# main.net
KiCad netlist of a schematic drawn in Altium Designer
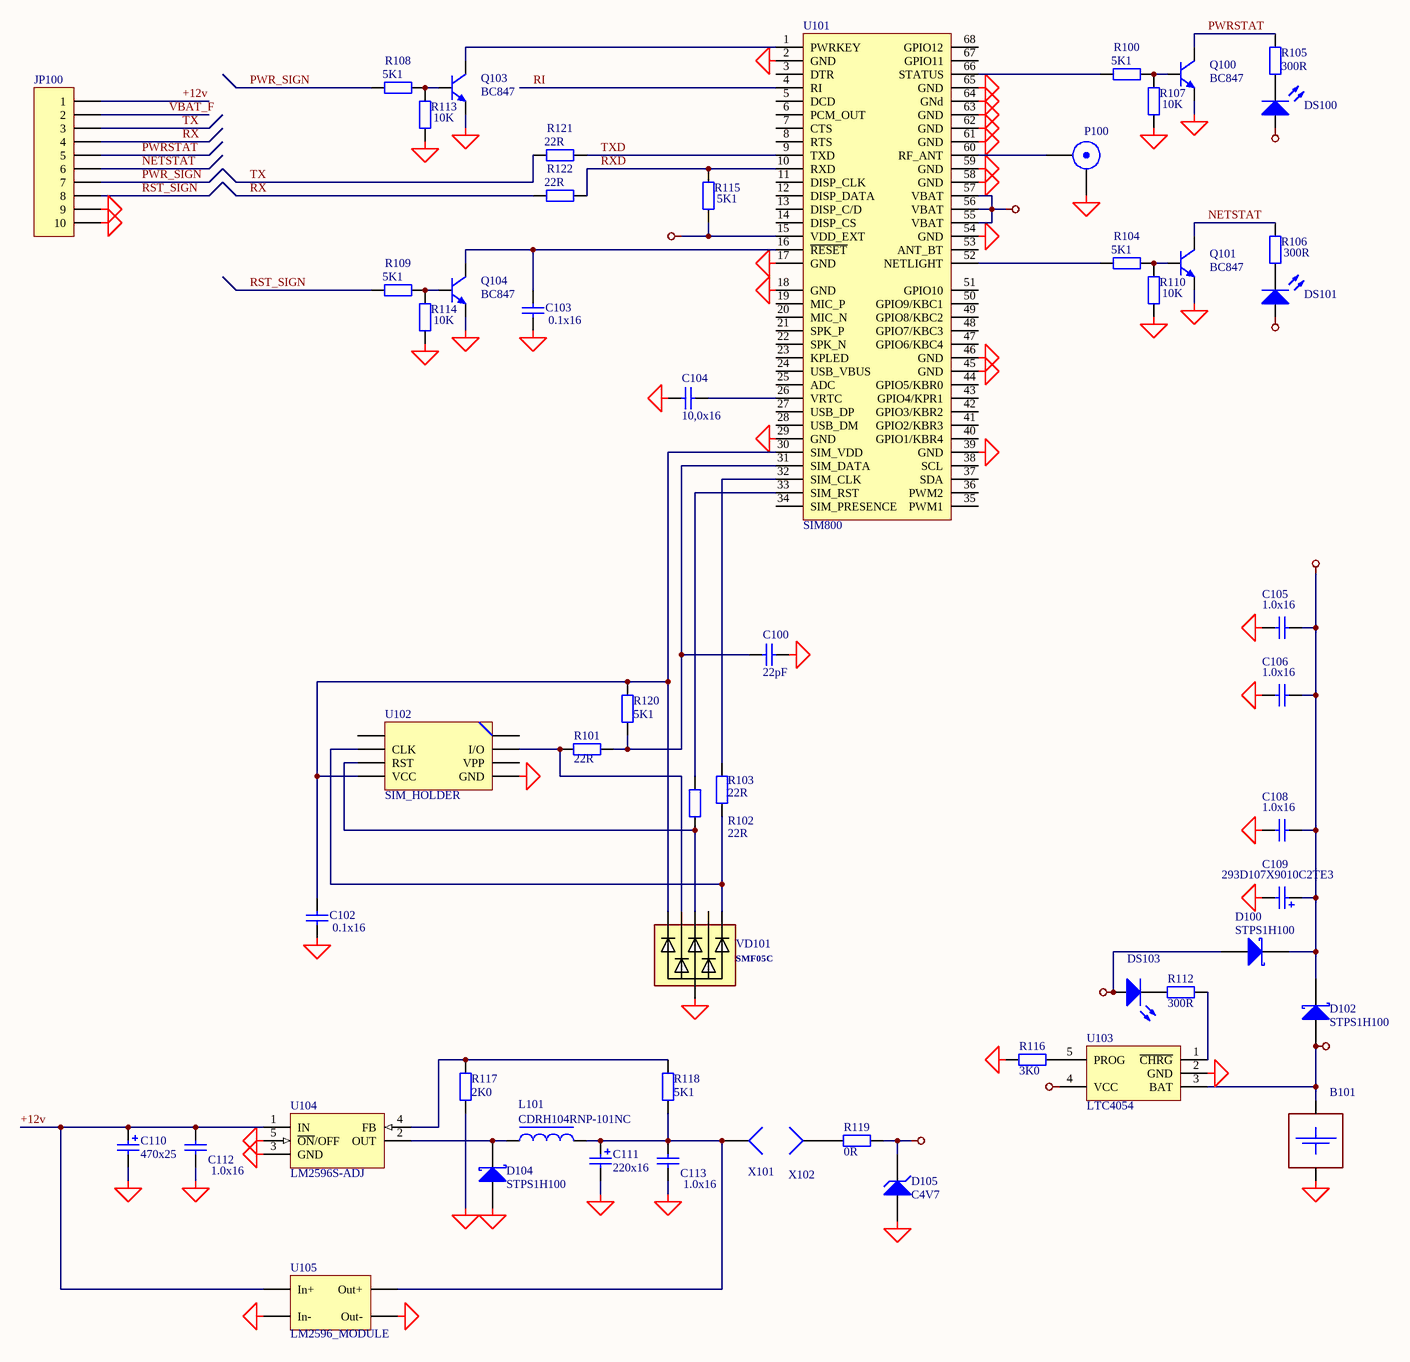
[diagram p0: main.SchDoc]

(export (version "E")
  (design (tool "Eeschema 10.0.6"))
  (components
    (comp (ref "B101")
      (value "BAT18650_HOLDER")
      (footprint "BAT18650_HOLDER")
      (libsource (lib "PAL") (part "BAT18650_HOLDER"))
    )
    (comp (ref "C100")
      (value "22pF")
      (footprint "_1206")
      (description "Capacitor")
      (fields (field (name "MANUFACTURER") "Generic Components") (field (name "PUBLISHER") "Altium Limited"))
      (libsource (lib "Miscellaneous Devices") (part "Cap Semi"))
    )
    (comp (ref "C102")
      (value "0.1x16")
      (footprint "_1206")
      (description "Capacitor")
      (fields (field (name "MANUFACTURER") "Generic Components") (field (name "PUBLISHER") "Altium Limited"))
      (libsource (lib "Miscellaneous Devices") (part "Cap Semi"))
    )
    (comp (ref "C103")
      (value "0.1x16")
      (footprint "_1206")
      (description "Capacitor")
      (fields (field (name "MANUFACTURER") "Generic Components") (field (name "PUBLISHER") "Altium Limited"))
      (libsource (lib "Miscellaneous Devices") (part "Cap Semi"))
    )
    (comp (ref "C104")
      (value "10,0x16")
      (footprint "_1206")
      (description "Capacitor")
      (fields (field (name "MANUFACTURER") "Generic Components") (field (name "PUBLISHER") "Altium Limited"))
      (libsource (lib "Miscellaneous Devices") (part "Cap Semi"))
    )
    (comp (ref "C105")
      (value "1.0x16")
      (footprint "_1206")
      (description "Capacitor")
      (fields (field (name "MANUFACTURER") "Generic Components") (field (name "PUBLISHER") "Altium Limited"))
      (libsource (lib "Miscellaneous Devices") (part "Cap Semi"))
    )
    (comp (ref "C106")
      (value "1.0x16")
      (footprint "_1206")
      (description "Capacitor")
      (fields (field (name "MANUFACTURER") "Generic Components") (field (name "PUBLISHER") "Altium Limited"))
      (libsource (lib "Miscellaneous Devices") (part "Cap Semi"))
    )
    (comp (ref "C108")
      (value "1.0x16")
      (footprint "_1206")
      (description "Capacitor")
      (fields (field (name "MANUFACTURER") "Generic Components") (field (name "PUBLISHER") "Altium Limited"))
      (libsource (lib "Miscellaneous Devices") (part "Cap Semi"))
    )
    (comp (ref "C109")
      (value "293D107X9010C2TE3")
      (footprint "CAP_EL_6_3")
      (description "Polarized Capacitor (Radial)")
      (fields (field (name "MANUFACTURER") "Generic Components") (field (name "PUBLISHER") "Altium Limited"))
      (libsource (lib "PAL") (part "Cap Pol1"))
    )
    (comp (ref "C110")
      (value "470x25")
      (footprint "el5")
      (description "Polarized Capacitor (Radial)")
      (fields (field (name "MANUFACTURER") "Generic Components") (field (name "PUBLISHER") "Altium Limited"))
      (libsource (lib "BUF") (part "Cap Pol"))
    )
    (comp (ref "C111")
      (value "220x16")
      (footprint "el3")
      (description "Polarized Capacitor (Radial)")
      (fields (field (name "MANUFACTURER") "Generic Components") (field (name "PUBLISHER") "Altium Limited"))
      (libsource (lib "BUF") (part "Cap Pol"))
    )
    (comp (ref "C112")
      (value "1.0x16")
      (footprint "_1206")
      (description "Capacitor")
      (fields (field (name "MANUFACTURER") "Generic Components") (field (name "PUBLISHER") "Altium Limited"))
      (libsource (lib "BUF") (part "Cap"))
    )
    (comp (ref "C113")
      (value "1.0x16")
      (footprint "_1206")
      (description "Capacitor")
      (fields (field (name "MANUFACTURER") "Generic Components") (field (name "PUBLISHER") "Altium Limited"))
      (libsource (lib "BUF") (part "Cap"))
    )
    (comp (ref "D100")
      (value "STPS1H100")
      (footprint "MBRS140")
      (description "Schottky Rectifier")
      (fields
        (field (name "MANUFACTURER") "International Rectifier")
        (field (name "PUBLISHER") "Altium Limited")
      )
      (libsource (lib "IR Discrete Diode") (part "10BQ015"))
    )
    (comp (ref "D102")
      (value "STPS1H100")
      (footprint "MBRS140")
      (description "Schottky Rectifier")
      (fields
        (field (name "MANUFACTURER") "International Rectifier")
        (field (name "PUBLISHER") "Altium Limited")
      )
      (libsource (lib "IR Discrete Diode") (part "10BQ015"))
    )
    (comp (ref "D104")
      (value "STPS1H100")
      (footprint "MBRS140")
      (description "Schottky Rectifier")
      (fields
        (field (name "MANUFACTURER") "International Rectifier")
        (field (name "PUBLISHER") "Altium Limited")
      )
      (libsource (lib "IR Discrete Diode") (part "10BQ015"))
    )
    (comp (ref "D105")
      (value "C4V7")
      (footprint "_1206d")
      (description "Zener Diode")
      (fields (field (name "MANUFACTURER") "Generic Components") (field (name "PUBLISHER") "Altium Limited"))
      (libsource (lib "Miscellaneous Devices") (part "D Zener"))
    )
    (comp (ref "DS100")
      (value "LED0")
      (footprint "el3")
      (description "Typical INFRARED GaAs LED")
      (fields (field (name "MANUFACTURER") "Generic Components") (field (name "PUBLISHER") "Altium Limited"))
      (libsource (lib "PAL") (part "LED0"))
    )
    (comp (ref "DS101")
      (value "LED0")
      (footprint "el3")
      (description "Typical INFRARED GaAs LED")
      (fields (field (name "MANUFACTURER") "Generic Components") (field (name "PUBLISHER") "Altium Limited"))
      (libsource (lib "PAL") (part "LED0"))
    )
    (comp (ref "DS103")
      (value "LED0")
      (footprint "el3")
      (description "Typical INFRARED GaAs LED")
      (fields (field (name "MANUFACTURER") "Generic Components") (field (name "PUBLISHER") "Altium Limited"))
      (libsource (lib "") (part "LED0_1"))
    )
    (comp (ref "JP100")
      (value "PLDH-10")
      (footprint "HDR2X5")
      (description "Header, 10-Pin")
      (fields (field (name "MANUFACTURER") "Generic Components") (field (name "PUBLISHER") "Altium Limited"))
      (libsource (lib "Miscellaneous Connectors") (part "Header 10"))
    )
    (comp (ref "L101")
      (value "CDRH104RNP-101NC")
      (footprint "CDRH104R")
      (description "Magnetic-Core Inductor")
      (fields (field (name "MANUFACTURER") "Generic Components") (field (name "PUBLISHER") "Altium Limited"))
      (libsource (lib "PAL") (part "Inductor Konstr 2"))
    )
    (comp (ref "P100")
      (value "SMB")
      (footprint "SMB_V-RJ45")
      (description "SMB Straight Connector")
      (fields (field (name "MANUFACTURER") "Generic Components") (field (name "PUBLISHER") "Altium Limited"))
      (libsource (lib "Miscellaneous Connectors") (part "SMB"))
    )
    (comp (ref "Q100")
      (value "BC847")
      (footprint "SO-G3")
      (description "General Purpose Transistor NPN Silicon")
      (fields (field (name "MANUFACTURER") "Motorola") (field (name "PUBLISHER") "Altium Limited"))
      (libsource (lib "PAL") (part "BC847ALT1"))
    )
    (comp (ref "Q101")
      (value "BC847")
      (footprint "SO-G3")
      (description "General Purpose Transistor NPN Silicon")
      (fields (field (name "MANUFACTURER") "Motorola") (field (name "PUBLISHER") "Altium Limited"))
      (libsource (lib "PAL") (part "BC847ALT1"))
    )
    (comp (ref "Q103")
      (value "BC847")
      (footprint "SO-G3")
      (description "General Purpose Transistor NPN Silicon")
      (fields (field (name "MANUFACTURER") "Motorola") (field (name "PUBLISHER") "Altium Limited"))
      (libsource (lib "PAL") (part "BC847ALT1"))
    )
    (comp (ref "Q104")
      (value "BC847")
      (footprint "SO-G3")
      (description "General Purpose Transistor NPN Silicon")
      (fields (field (name "MANUFACTURER") "Motorola") (field (name "PUBLISHER") "Altium Limited"))
      (libsource (lib "PAL") (part "BC847ALT1"))
    )
    (comp (ref "R100")
      (value "5K1")
      (footprint "_1206")
      (description "Resistor")
      (fields (field (name "MANUFACTURER") "Generic Components") (field (name "PUBLISHER") "Altium Limited"))
      (libsource (lib "") (part "Res2_1"))
    )
    (comp (ref "R101")
      (value "22R")
      (footprint "_1206")
      (description "Resistor")
      (fields (field (name "MANUFACTURER") "Generic Components") (field (name "PUBLISHER") "Altium Limited"))
      (libsource (lib "Miscellaneous Devices") (part "Res2"))
    )
    (comp (ref "R102")
      (value "22R")
      (footprint "_1206")
      (description "Resistor")
      (fields (field (name "MANUFACTURER") "Generic Components") (field (name "PUBLISHER") "Altium Limited"))
      (libsource (lib "") (part "Res2_1"))
    )
    (comp (ref "R103")
      (value "22R")
      (footprint "_1206")
      (description "Resistor")
      (fields (field (name "MANUFACTURER") "Generic Components") (field (name "PUBLISHER") "Altium Limited"))
      (libsource (lib "") (part "Res2_1"))
    )
    (comp (ref "R104")
      (value "5K1")
      (footprint "_1206")
      (description "Resistor")
      (fields (field (name "MANUFACTURER") "Generic Components") (field (name "PUBLISHER") "Altium Limited"))
      (libsource (lib "") (part "Res2_1"))
    )
    (comp (ref "R105")
      (value "300R")
      (footprint "_1206")
      (description "Resistor")
      (fields (field (name "MANUFACTURER") "Generic Components") (field (name "PUBLISHER") "Altium Limited"))
      (libsource (lib "") (part "Res2_2"))
    )
    (comp (ref "R106")
      (value "300R")
      (footprint "_1206")
      (description "Resistor")
      (fields (field (name "MANUFACTURER") "Generic Components") (field (name "PUBLISHER") "Altium Limited"))
      (libsource (lib "Miscellaneous Devices") (part "Res2"))
    )
    (comp (ref "R107")
      (value "10K")
      (footprint "_1206")
      (description "Resistor")
      (fields (field (name "MANUFACTURER") "Generic Components") (field (name "PUBLISHER") "Altium Limited"))
      (libsource (lib "Miscellaneous Devices") (part "Res2"))
    )
    (comp (ref "R108")
      (value "5K1")
      (footprint "_1206")
      (description "Resistor")
      (fields (field (name "MANUFACTURER") "Generic Components") (field (name "PUBLISHER") "Altium Limited"))
      (libsource (lib "") (part "Res2_1"))
    )
    (comp (ref "R109")
      (value "5K1")
      (footprint "_1206")
      (description "Resistor")
      (fields (field (name "MANUFACTURER") "Generic Components") (field (name "PUBLISHER") "Altium Limited"))
      (libsource (lib "") (part "Res2_1"))
    )
    (comp (ref "R110")
      (value "10K")
      (footprint "_1206")
      (description "Resistor")
      (fields (field (name "MANUFACTURER") "Generic Components") (field (name "PUBLISHER") "Altium Limited"))
      (libsource (lib "Miscellaneous Devices") (part "Res2"))
    )
    (comp (ref "R112")
      (value "300R")
      (footprint "_1206")
      (description "Resistor")
      (fields (field (name "MANUFACTURER") "Generic Components") (field (name "PUBLISHER") "Altium Limited"))
      (libsource (lib "") (part "Res2_3"))
    )
    (comp (ref "R113")
      (value "10K")
      (footprint "_1206")
      (description "Resistor")
      (fields (field (name "MANUFACTURER") "Generic Components") (field (name "PUBLISHER") "Altium Limited"))
      (libsource (lib "Miscellaneous Devices") (part "Res2"))
    )
    (comp (ref "R114")
      (value "10K")
      (footprint "_1206")
      (description "Resistor")
      (fields (field (name "MANUFACTURER") "Generic Components") (field (name "PUBLISHER") "Altium Limited"))
      (libsource (lib "Miscellaneous Devices") (part "Res2"))
    )
    (comp (ref "R115")
      (value "5K1")
      (footprint "_1206")
      (description "Resistor")
      (fields (field (name "MANUFACTURER") "Generic Components") (field (name "PUBLISHER") "Altium Limited"))
      (libsource (lib "Miscellaneous Devices") (part "Res2"))
    )
    (comp (ref "R116")
      (value "3K0")
      (footprint "_1206")
      (description "Resistor")
      (fields (field (name "MANUFACTURER") "Generic Components") (field (name "PUBLISHER") "Altium Limited"))
      (libsource (lib "") (part "Res2_3"))
    )
    (comp (ref "R117")
      (value "2K0")
      (footprint "_1206")
      (description "Resistor")
      (fields (field (name "MANUFACTURER") "Generic Components") (field (name "PUBLISHER") "Altium Limited"))
      (libsource (lib "") (part "Res2_1"))
    )
    (comp (ref "R118")
      (value "5K1")
      (footprint "_1206")
      (description "Resistor")
      (fields (field (name "MANUFACTURER") "Generic Components") (field (name "PUBLISHER") "Altium Limited"))
      (libsource (lib "") (part "Res2_1"))
    )
    (comp (ref "R119")
      (value "0R")
      (footprint "_1206")
      (description "Resistor")
      (fields (field (name "MANUFACTURER") "Generic Components") (field (name "PUBLISHER") "Altium Limited"))
      (libsource (lib "") (part "Res2_2"))
    )
    (comp (ref "R120")
      (value "5K1")
      (footprint "_1206")
      (description "Resistor")
      (fields (field (name "MANUFACTURER") "Generic Components") (field (name "PUBLISHER") "Altium Limited"))
      (libsource (lib "") (part "Res2_1"))
    )
    (comp (ref "R121")
      (value "22R")
      (footprint "_1206")
      (description "Resistor")
      (fields (field (name "MANUFACTURER") "Generic Components") (field (name "PUBLISHER") "Altium Limited"))
      (libsource (lib "") (part "Res2_1"))
    )
    (comp (ref "R122")
      (value "22R")
      (footprint "_1206")
      (description "Resistor")
      (fields (field (name "MANUFACTURER") "Generic Components") (field (name "PUBLISHER") "Altium Limited"))
      (libsource (lib "") (part "Res2_1"))
    )
    (comp (ref "U101") (value "SIM800") (footprint "SIM800") (libsource (lib "PAL") (part "SIM800")))
    (comp (ref "U102")
      (value "SIM_HOLDER")
      (footprint "SIM_HOLDER_1")
      (libsource (lib "Schlib1") (part "SIM_HOLDER"))
    )
    (comp (ref "U103") (value "LTC4054") (footprint "SO-G5/P.95") (libsource (lib "PAL") (part "LTC4054")))
    (comp (ref "U104")
      (value "LM2596S-ADJ")
      (footprint "SIP-G5/Y2.1")
      (description "Simple Switcher Power Converter 150 kHz 3A Step Down Voltage Regulator")
      (fields
        (field (name "MANUFACTURER") "National Semiconductor")
        (field (name "PUBLISHER") "Altium Limited")
      )
      (libsource (lib "NSC Power Mgt Switching Regulator") (part "LM2596S-ADJ"))
    )
    (comp (ref "U105")
      (value "LM2596_MODULE")
      (footprint "LM2596_MODULE_1")
      (libsource (lib "PAL") (part "LM2596_MODULE"))
    )
    (comp (ref "VD101")
      (value "SMF05C")
      (footprint "sot363")
      (fields (field (name "MANUFACTURERPARTNUMBER") "SMF05C"))
      (libsource (lib "PAL") (part "SMF05C"))
    )
    (comp (ref "X101")
      (value "Socket")
      (footprint "PIN1")
      (fields (field (name "MANUFACTURER") "Generic Components") (field (name "PUBLISHER") "Altium Limited"))
      (libsource (lib "Miscellaneous Connectors") (part "Socket"))
    )
    (comp (ref "X102")
      (value "Socket")
      (footprint "PIN1")
      (fields (field (name "MANUFACTURER") "Generic Components") (field (name "PUBLISHER") "Altium Limited"))
      (libsource (lib "Miscellaneous Connectors") (part "Socket"))
    )
  )
  (nets
    (net (code "1") (name "+5v") (class "Default")
      (node (ref "D100") (pin "1") (pinfunction "A_1") (pintype "passive"))
      (node (ref "D105") (pin "2") (pinfunction "K_2") (pintype "passive"))
      (node (ref "DS103") (pin "1") (pinfunction "A_1") (pintype "passive"))
      (node (ref "R119") (pin "2") (pinfunction "2_2") (pintype "passive"))
      (node (ref "U103") (pin "4") (pinfunction "VCC_4") (pintype "passive"))
    )
    (net (code "2") (name "/+12v") (class "Default")
      (node (ref "C110") (pin "1") (pinfunction "1_1") (pintype "passive"))
      (node (ref "C112") (pin "2") (pinfunction "2_2") (pintype "passive"))
      (node (ref "JP100") (pin "1") (pinfunction "1_1") (pintype "passive"))
      (node (ref "U104") (pin "1") (pinfunction "IN_1") (pintype "power_in"))
      (node (ref "U105") (pin "1") (pinfunction "In+_1") (pintype "passive"))
    )
    (net (code "3") (name "/NETSTAT") (class "Default")
      (node (ref "JP100") (pin "6") (pinfunction "6_6") (pintype "passive"))
      (node (ref "Q101") (pin "3") (pinfunction "C_3") (pintype "passive"))
      (node (ref "R106") (pin "1") (pinfunction "1_1") (pintype "passive"))
    )
    (net (code "4") (name "/PWRSTAT") (class "Default")
      (node (ref "JP100") (pin "5") (pinfunction "5_5") (pintype "passive"))
      (node (ref "Q100") (pin "3") (pinfunction "C_3") (pintype "passive"))
      (node (ref "R105") (pin "2") (pinfunction "2_2") (pintype "passive"))
    )
    (net (code "5") (name "/PWR_SIGN") (class "Default")
      (node (ref "JP100") (pin "7") (pinfunction "7_7") (pintype "passive"))
      (node (ref "R108") (pin "2") (pinfunction "2_2") (pintype "passive"))
    )
    (net (code "6") (name "/RI") (class "Default")
      (node (ref "U101") (pin "4") (pinfunction "RI_4") (pintype "passive"))
    )
    (net (code "7") (name "/RST_SIGN") (class "Default")
      (node (ref "JP100") (pin "8") (pinfunction "8_8") (pintype "passive"))
      (node (ref "R109") (pin "2") (pinfunction "2_2") (pintype "passive"))
    )
    (net (code "8") (name "/RX") (class "Default")
      (node (ref "JP100") (pin "4") (pinfunction "4_4") (pintype "passive"))
      (node (ref "R122") (pin "2") (pinfunction "2_2") (pintype "passive"))
    )
    (net (code "9") (name "/RXD") (class "Default")
      (node (ref "R115") (pin "1") (pinfunction "1_1") (pintype "passive"))
      (node (ref "R122") (pin "1") (pinfunction "1_1") (pintype "passive"))
      (node (ref "U101") (pin "10") (pinfunction "RXD_10") (pintype "passive"))
    )
    (net (code "10") (name "/TX") (class "Default")
      (node (ref "JP100") (pin "3") (pinfunction "3_3") (pintype "passive"))
      (node (ref "R121") (pin "2") (pinfunction "2_2") (pintype "passive"))
    )
    (net (code "11") (name "/TXD") (class "Default")
      (node (ref "R121") (pin "1") (pinfunction "1_1") (pintype "passive"))
      (node (ref "U101") (pin "9") (pinfunction "TXD_9") (pintype "passive"))
    )
    (net (code "12") (name "GND") (class "Default")
      (node (ref "B101") (pin "2") (pinfunction "-_2") (pintype "passive"))
      (node (ref "C100") (pin "1") (pinfunction "1_1") (pintype "passive"))
      (node (ref "C102") (pin "1") (pinfunction "1_1") (pintype "passive"))
      (node (ref "C103") (pin "1") (pinfunction "1_1") (pintype "passive"))
      (node (ref "C104") (pin "2") (pinfunction "2_2") (pintype "passive"))
      (node (ref "C105") (pin "1") (pinfunction "1_1") (pintype "passive"))
      (node (ref "C106") (pin "1") (pinfunction "1_1") (pintype "passive"))
      (node (ref "C108") (pin "1") (pinfunction "1_1") (pintype "passive"))
      (node (ref "C109") (pin "2") (pinfunction "2_2") (pintype "passive"))
      (node (ref "C110") (pin "2") (pinfunction "2_2") (pintype "passive"))
      (node (ref "C111") (pin "2") (pinfunction "2_2") (pintype "passive"))
      (node (ref "C112") (pin "1") (pinfunction "1_1") (pintype "passive"))
      (node (ref "C113") (pin "1") (pinfunction "1_1") (pintype "passive"))
      (node (ref "D104") (pin "1") (pinfunction "A_1") (pintype "passive"))
      (node (ref "D105") (pin "1") (pinfunction "A_1") (pintype "passive"))
      (node (ref "JP100") (pin "10") (pinfunction "10_10") (pintype "passive"))
      (node (ref "JP100") (pin "9") (pinfunction "9_9") (pintype "passive"))
      (node (ref "P100") (pin "2") (pinfunction "Y_2") (pintype "passive"))
      (node (ref "Q100") (pin "2") (pinfunction "E_2") (pintype "passive"))
      (node (ref "Q101") (pin "2") (pinfunction "E_2") (pintype "passive"))
      (node (ref "Q103") (pin "2") (pinfunction "E_2") (pintype "passive"))
      (node (ref "Q104") (pin "2") (pinfunction "E_2") (pintype "passive"))
      (node (ref "R107") (pin "2") (pinfunction "2_2") (pintype "passive"))
      (node (ref "R110") (pin "2") (pinfunction "2_2") (pintype "passive"))
      (node (ref "R113") (pin "2") (pinfunction "2_2") (pintype "passive"))
      (node (ref "R114") (pin "2") (pinfunction "2_2") (pintype "passive"))
      (node (ref "R116") (pin "2") (pinfunction "2_2") (pintype "passive"))
      (node (ref "R117") (pin "2") (pinfunction "2_2") (pintype "passive"))
      (node (ref "U101") (pin "17") (pinfunction "GND_17") (pintype "passive"))
      (node (ref "U101") (pin "18") (pinfunction "GND_18") (pintype "passive"))
      (node (ref "U101") (pin "2") (pinfunction "GND_2") (pintype "passive"))
      (node (ref "U101") (pin "29") (pinfunction "GND_29") (pintype "passive"))
      (node (ref "U101") (pin "39") (pinfunction "GND_39") (pintype "passive"))
      (node (ref "U101") (pin "45") (pinfunction "GND_45") (pintype "passive"))
      (node (ref "U101") (pin "46") (pinfunction "GND_46") (pintype "passive"))
      (node (ref "U101") (pin "54") (pinfunction "GND_54") (pintype "passive"))
      (node (ref "U101") (pin "58") (pinfunction "GND_58") (pintype "passive"))
      (node (ref "U101") (pin "59") (pinfunction "GND_59") (pintype "passive"))
      (node (ref "U101") (pin "61") (pinfunction "GND_61") (pintype "passive"))
      (node (ref "U101") (pin "62") (pinfunction "GND_62") (pintype "passive"))
      (node (ref "U101") (pin "63") (pinfunction "GND_63") (pintype "passive"))
      (node (ref "U101") (pin "64") (pinfunction "GNd_64") (pintype "passive"))
      (node (ref "U101") (pin "65") (pinfunction "GND_65") (pintype "passive"))
      (node (ref "U102") (pin "5") (pinfunction "GND_5") (pintype "passive"))
      (node (ref "U103") (pin "2") (pinfunction "GND_2") (pintype "passive"))
      (node (ref "U104") (pin "3") (pinfunction "GND_3") (pintype "power_in"))
      (node (ref "U104") (pin "5") (pinfunction "~{ON}/OFF_5") (pintype "input"))
      (node (ref "U105") (pin "2") (pinfunction "In-_2") (pintype "passive"))
      (node (ref "U105") (pin "3") (pinfunction "Out-_3") (pintype "passive"))
      (node (ref "VD101") (pin "2") (pinfunction "2_2") (pintype "passive"))
    )
    (net (code "13") (name "Net-(D104-K)") (class "Default")
      (node (ref "D104") (pin "2") (pinfunction "K_2") (pintype "passive"))
      (node (ref "L101") (pin "1") (pinfunction "1_1") (pintype "passive"))
      (node (ref "U104") (pin "2") (pinfunction "OUT_2") (pintype "power_in"))
    )
    (net (code "14") (name "Net-(DS100-K)") (class "Default")
      (node (ref "DS100") (pin "2") (pinfunction "K_2") (pintype "passive"))
      (node (ref "R105") (pin "1") (pinfunction "1_1") (pintype "passive"))
    )
    (net (code "15") (name "Net-(DS101-K)") (class "Default")
      (node (ref "DS101") (pin "2") (pinfunction "K_2") (pintype "passive"))
      (node (ref "R106") (pin "2") (pinfunction "2_2") (pintype "passive"))
    )
    (net (code "16") (name "Net-(DS103-K)") (class "Default")
      (node (ref "DS103") (pin "2") (pinfunction "K_2") (pintype "passive"))
      (node (ref "R112") (pin "2") (pinfunction "2_2") (pintype "passive"))
    )
    (net (code "17") (name "Net-(P100-X)") (class "Default")
      (node (ref "P100") (pin "1") (pinfunction "X_1") (pintype "passive"))
      (node (ref "U101") (pin "60") (pinfunction "RF_ANT_60") (pintype "passive"))
    )
    (net (code "18") (name "Net-(Q100-B)") (class "Default")
      (node (ref "Q100") (pin "1") (pinfunction "B_1") (pintype "passive"))
      (node (ref "R100") (pin "1") (pinfunction "1_1") (pintype "passive"))
      (node (ref "R107") (pin "1") (pinfunction "1_1") (pintype "passive"))
    )
    (net (code "19") (name "Net-(Q101-B)") (class "Default")
      (node (ref "Q101") (pin "1") (pinfunction "B_1") (pintype "passive"))
      (node (ref "R104") (pin "1") (pinfunction "1_1") (pintype "passive"))
      (node (ref "R110") (pin "1") (pinfunction "1_1") (pintype "passive"))
    )
    (net (code "20") (name "Net-(Q103-B)") (class "Default")
      (node (ref "Q103") (pin "1") (pinfunction "B_1") (pintype "passive"))
      (node (ref "R108") (pin "1") (pinfunction "1_1") (pintype "passive"))
      (node (ref "R113") (pin "1") (pinfunction "1_1") (pintype "passive"))
    )
    (net (code "21") (name "Net-(Q103-C)") (class "Default")
      (node (ref "Q103") (pin "3") (pinfunction "C_3") (pintype "passive"))
      (node (ref "U101") (pin "1") (pinfunction "PWRKEY_1") (pintype "passive"))
    )
    (net (code "22") (name "Net-(Q104-B)") (class "Default")
      (node (ref "Q104") (pin "1") (pinfunction "B_1") (pintype "passive"))
      (node (ref "R109") (pin "1") (pinfunction "1_1") (pintype "passive"))
      (node (ref "R114") (pin "1") (pinfunction "1_1") (pintype "passive"))
    )
    (net (code "23") (name "Net-(Q104-C)") (class "Default")
      (node (ref "C103") (pin "2") (pinfunction "2_2") (pintype "passive"))
      (node (ref "Q104") (pin "3") (pinfunction "C_3") (pintype "passive"))
      (node (ref "U101") (pin "16") (pinfunction "~{RESET}_16") (pintype "passive"))
    )
    (net (code "24") (name "Net-(R119-Pad1)") (class "Default")
      (node (ref "R119") (pin "1") (pinfunction "1_1") (pintype "passive"))
      (node (ref "X102") (pin "1") (pinfunction "1_1") (pintype "passive"))
    )
    (net (code "25") (name "Net-(U101-NETLIGHT)") (class "Default")
      (node (ref "R104") (pin "2") (pinfunction "2_2") (pintype "passive"))
      (node (ref "U101") (pin "52") (pinfunction "NETLIGHT_52") (pintype "passive"))
    )
    (net (code "26") (name "Net-(U101-SIM_CLK)") (class "Default")
      (node (ref "R103") (pin "1") (pinfunction "1_1") (pintype "passive"))
      (node (ref "U101") (pin "32") (pinfunction "SIM_CLK_32") (pintype "passive"))
    )
    (net (code "27") (name "Net-(U101-SIM_DATA)") (class "Default")
      (node (ref "C100") (pin "2") (pinfunction "2_2") (pintype "passive"))
      (node (ref "R101") (pin "1") (pinfunction "1_1") (pintype "passive"))
      (node (ref "R120") (pin "2") (pinfunction "2_2") (pintype "passive"))
      (node (ref "U101") (pin "31") (pinfunction "SIM_DATA_31") (pintype "passive"))
    )
    (net (code "28") (name "Net-(U101-SIM_RST)") (class "Default")
      (node (ref "R102") (pin "1") (pinfunction "1_1") (pintype "passive"))
      (node (ref "U101") (pin "33") (pinfunction "SIM_RST_33") (pintype "passive"))
    )
    (net (code "29") (name "Net-(U101-SIM_VDD)") (class "Default")
      (node (ref "C102") (pin "2") (pinfunction "2_2") (pintype "passive"))
      (node (ref "R120") (pin "1") (pinfunction "1_1") (pintype "passive"))
      (node (ref "U101") (pin "30") (pinfunction "SIM_VDD_30") (pintype "passive"))
      (node (ref "U102") (pin "4") (pinfunction "VCC_4") (pintype "passive"))
      (node (ref "VD101") (pin "1") (pinfunction "1_1") (pintype "passive"))
    )
    (net (code "30") (name "Net-(U101-STATUS)") (class "Default")
      (node (ref "R100") (pin "2") (pinfunction "2_2") (pintype "passive"))
      (node (ref "U101") (pin "66") (pinfunction "STATUS_66") (pintype "passive"))
    )
    (net (code "31") (name "Net-(U101-VRTC)") (class "Default")
      (node (ref "C104") (pin "1") (pinfunction "1_1") (pintype "passive"))
      (node (ref "U101") (pin "26") (pinfunction "VRTC_26") (pintype "passive"))
    )
    (net (code "32") (name "Net-(U102-CLK)") (class "Default")
      (node (ref "R103") (pin "2") (pinfunction "2_2") (pintype "passive"))
      (node (ref "U102") (pin "2") (pinfunction "CLK_2") (pintype "passive"))
      (node (ref "VD101") (pin "6") (pinfunction "6_6") (pintype "passive"))
    )
    (net (code "33") (name "Net-(U102-I{slash}O)") (class "Default")
      (node (ref "R101") (pin "2") (pinfunction "2_2") (pintype "passive"))
      (node (ref "U102") (pin "7") (pinfunction "I/O_7") (pintype "passive"))
      (node (ref "VD101") (pin "3") (pinfunction "3_3") (pintype "passive"))
    )
    (net (code "34") (name "Net-(U102-RST)") (class "Default")
      (node (ref "R102") (pin "2") (pinfunction "2_2") (pintype "passive"))
      (node (ref "U102") (pin "3") (pinfunction "RST_3") (pintype "passive"))
      (node (ref "VD101") (pin "4") (pinfunction "4_4") (pintype "passive"))
    )
    (net (code "35") (name "Net-(U103-PROG)") (class "Default")
      (node (ref "R116") (pin "1") (pinfunction "1_1") (pintype "passive"))
      (node (ref "U103") (pin "5") (pinfunction "PROG_5") (pintype "passive"))
    )
    (net (code "36") (name "Net-(U103-~{CHRG})") (class "Default")
      (node (ref "R112") (pin "1") (pinfunction "1_1") (pintype "passive"))
      (node (ref "U103") (pin "1") (pinfunction "~{CHRG}_1") (pintype "passive"))
    )
    (net (code "37") (name "Net-(U104-FB)") (class "Default")
      (node (ref "R117") (pin "1") (pinfunction "1_1") (pintype "passive"))
      (node (ref "R118") (pin "1") (pinfunction "1_1") (pintype "passive"))
      (node (ref "U104") (pin "4") (pinfunction "FB_4") (pintype "input"))
    )
    (net (code "38") (name "Net-(U105-Out+)") (class "Default")
      (node (ref "C111") (pin "1") (pinfunction "1_1") (pintype "passive"))
      (node (ref "C113") (pin "2") (pinfunction "2_2") (pintype "passive"))
      (node (ref "L101") (pin "2") (pinfunction "2_2") (pintype "passive"))
      (node (ref "R118") (pin "2") (pinfunction "2_2") (pintype "passive"))
      (node (ref "U105") (pin "4") (pinfunction "Out+_4") (pintype "passive"))
      (node (ref "X101") (pin "1") (pinfunction "1_1") (pintype "passive"))
    )
    (net (code "39") (name "VBAT") (class "Default")
      (node (ref "C105") (pin "2") (pinfunction "2_2") (pintype "passive"))
      (node (ref "C106") (pin "2") (pinfunction "2_2") (pintype "passive"))
      (node (ref "C108") (pin "2") (pinfunction "2_2") (pintype "passive"))
      (node (ref "C109") (pin "1") (pinfunction "1_1") (pintype "passive"))
      (node (ref "D100") (pin "2") (pinfunction "K_2") (pintype "passive"))
      (node (ref "D102") (pin "2") (pinfunction "K_2") (pintype "passive"))
      (node (ref "DS100") (pin "1") (pinfunction "A_1") (pintype "passive"))
      (node (ref "DS101") (pin "1") (pinfunction "A_1") (pintype "passive"))
      (node (ref "U101") (pin "55") (pinfunction "VBAT_55") (pintype "passive"))
      (node (ref "U101") (pin "56") (pinfunction "VBAT_56") (pintype "passive"))
      (node (ref "U101") (pin "57") (pinfunction "VBAT_57") (pintype "passive"))
    )
    (net (code "40") (name "VBAT_F") (class "Default")
      (node (ref "B101") (pin "1") (pinfunction "+_1") (pintype "passive"))
      (node (ref "D102") (pin "1") (pinfunction "A_1") (pintype "passive"))
      (node (ref "JP100") (pin "2") (pinfunction "2_2") (pintype "passive"))
      (node (ref "U103") (pin "3") (pinfunction "BAT_3") (pintype "passive"))
    )
    (net (code "41") (name "VDD_EXT") (class "Default")
      (node (ref "R115") (pin "2") (pinfunction "2_2") (pintype "passive"))
      (node (ref "U101") (pin "15") (pinfunction "VDD_EXT_15") (pintype "passive"))
    )
    (net (code "42") (name "unconnected-(U101-ADC-Pad25)") (class "Default")
      (node (ref "U101") (pin "25") (pinfunction "ADC_25") (pintype "passive"))
    )
    (net (code "43") (name "unconnected-(U101-ANT_BT-Pad53)") (class "Default")
      (node (ref "U101") (pin "53") (pinfunction "ANT_BT_53") (pintype "passive"))
    )
    (net (code "44") (name "unconnected-(U101-CTS-Pad7)") (class "Default")
      (node (ref "U101") (pin "7") (pinfunction "CTS_7") (pintype "passive"))
    )
    (net (code "45") (name "unconnected-(U101-DCD-Pad5)") (class "Default")
      (node (ref "U101") (pin "5") (pinfunction "DCD_5") (pintype "passive"))
    )
    (net (code "46") (name "unconnected-(U101-DISP_CLK-Pad11)") (class "Default")
      (node (ref "U101") (pin "11") (pinfunction "DISP_CLK_11") (pintype "passive"))
    )
    (net (code "47") (name "unconnected-(U101-DISP_CS-Pad14)") (class "Default")
      (node (ref "U101") (pin "14") (pinfunction "DISP_CS_14") (pintype "passive"))
    )
    (net (code "48") (name "unconnected-(U101-DISP_C{slash}D-Pad13)") (class "Default")
      (node (ref "U101") (pin "13") (pinfunction "DISP_C/D_13") (pintype "passive"))
    )
    (net (code "49") (name "unconnected-(U101-DISP_DATA-Pad12)") (class "Default")
      (node (ref "U101") (pin "12") (pinfunction "DISP_DATA_12") (pintype "passive"))
    )
    (net (code "50") (name "unconnected-(U101-DTR-Pad3)") (class "Default")
      (node (ref "U101") (pin "3") (pinfunction "DTR_3") (pintype "passive"))
    )
    (net (code "51") (name "unconnected-(U101-GPIO1{slash}KBR4-Pad40)") (class "Default")
      (node (ref "U101") (pin "40") (pinfunction "GPIO1/KBR4_40") (pintype "passive"))
    )
    (net (code "52") (name "unconnected-(U101-GPIO2{slash}KBR3-Pad41)") (class "Default")
      (node (ref "U101") (pin "41") (pinfunction "GPIO2/KBR3_41") (pintype "passive"))
    )
    (net (code "53") (name "unconnected-(U101-GPIO3{slash}KBR2-Pad42)") (class "Default")
      (node (ref "U101") (pin "42") (pinfunction "GPIO3/KBR2_42") (pintype "passive"))
    )
    (net (code "54") (name "unconnected-(U101-GPIO4{slash}KPR1-Pad43)") (class "Default")
      (node (ref "U101") (pin "43") (pinfunction "GPIO4/KPR1_43") (pintype "passive"))
    )
    (net (code "55") (name "unconnected-(U101-GPIO5{slash}KBR0-Pad44)") (class "Default")
      (node (ref "U101") (pin "44") (pinfunction "GPIO5/KBR0_44") (pintype "passive"))
    )
    (net (code "56") (name "unconnected-(U101-GPIO6{slash}KBC4-Pad47)") (class "Default")
      (node (ref "U101") (pin "47") (pinfunction "GPIO6/KBC4_47") (pintype "passive"))
    )
    (net (code "57") (name "unconnected-(U101-GPIO7{slash}KBC3-Pad48)") (class "Default")
      (node (ref "U101") (pin "48") (pinfunction "GPIO7/KBC3_48") (pintype "passive"))
    )
    (net (code "58") (name "unconnected-(U101-GPIO8{slash}KBC2-Pad49)") (class "Default")
      (node (ref "U101") (pin "49") (pinfunction "GPIO8/KBC2_49") (pintype "passive"))
    )
    (net (code "59") (name "unconnected-(U101-GPIO9{slash}KBC1-Pad50)") (class "Default")
      (node (ref "U101") (pin "50") (pinfunction "GPIO9/KBC1_50") (pintype "passive"))
    )
    (net (code "60") (name "unconnected-(U101-GPIO10-Pad51)") (class "Default")
      (node (ref "U101") (pin "51") (pinfunction "GPIO10_51") (pintype "passive"))
    )
    (net (code "61") (name "unconnected-(U101-GPIO11-Pad67)") (class "Default")
      (node (ref "U101") (pin "67") (pinfunction "GPIO11_67") (pintype "passive"))
    )
    (net (code "62") (name "unconnected-(U101-GPIO12-Pad68)") (class "Default")
      (node (ref "U101") (pin "68") (pinfunction "GPIO12_68") (pintype "passive"))
    )
    (net (code "63") (name "unconnected-(U101-KPLED-Pad23)") (class "Default")
      (node (ref "U101") (pin "23") (pinfunction "KPLED_23") (pintype "passive"))
    )
    (net (code "64") (name "unconnected-(U101-MIC_N-Pad20)") (class "Default")
      (node (ref "U101") (pin "20") (pinfunction "MIC_N_20") (pintype "passive"))
    )
    (net (code "65") (name "unconnected-(U101-MIC_P-Pad19)") (class "Default")
      (node (ref "U101") (pin "19") (pinfunction "MIC_P_19") (pintype "passive"))
    )
    (net (code "66") (name "unconnected-(U101-PCM_OUT-Pad6)") (class "Default")
      (node (ref "U101") (pin "6") (pinfunction "PCM_OUT_6") (pintype "passive"))
    )
    (net (code "67") (name "unconnected-(U101-PWM1-Pad35)") (class "Default")
      (node (ref "U101") (pin "35") (pinfunction "PWM1_35") (pintype "passive"))
    )
    (net (code "68") (name "unconnected-(U101-PWM2-Pad36)") (class "Default")
      (node (ref "U101") (pin "36") (pinfunction "PWM2_36") (pintype "passive"))
    )
    (net (code "69") (name "unconnected-(U101-RTS-Pad8)") (class "Default")
      (node (ref "U101") (pin "8") (pinfunction "RTS_8") (pintype "passive"))
    )
    (net (code "70") (name "unconnected-(U101-SCL-Pad38)") (class "Default")
      (node (ref "U101") (pin "38") (pinfunction "SCL_38") (pintype "passive"))
    )
    (net (code "71") (name "unconnected-(U101-SDA-Pad37)") (class "Default")
      (node (ref "U101") (pin "37") (pinfunction "SDA_37") (pintype "passive"))
    )
    (net (code "72") (name "unconnected-(U101-SIM_PRESENCE-Pad34)") (class "Default")
      (node (ref "U101") (pin "34") (pinfunction "SIM_PRESENCE_34") (pintype "passive"))
    )
    (net (code "73") (name "unconnected-(U101-SPK_N-Pad22)") (class "Default")
      (node (ref "U101") (pin "22") (pinfunction "SPK_N_22") (pintype "passive"))
    )
    (net (code "74") (name "unconnected-(U101-SPK_P-Pad21)") (class "Default")
      (node (ref "U101") (pin "21") (pinfunction "SPK_P_21") (pintype "passive"))
    )
    (net (code "75") (name "unconnected-(U101-USB_DM-Pad28)") (class "Default")
      (node (ref "U101") (pin "28") (pinfunction "USB_DM_28") (pintype "passive"))
    )
    (net (code "76") (name "unconnected-(U101-USB_DP-Pad27)") (class "Default")
      (node (ref "U101") (pin "27") (pinfunction "USB_DP_27") (pintype "passive"))
    )
    (net (code "77") (name "unconnected-(U101-USB_VBUS-Pad24)") (class "Default")
      (node (ref "U101") (pin "24") (pinfunction "USB_VBUS_24") (pintype "passive"))
    )
    (net (code "78") (name "unconnected-(U102-Pad1)") (class "Default")
      (node (ref "U102") (pin "1") (pintype "passive"))
    )
    (net (code "79") (name "unconnected-(U102-Pad8)") (class "Default")
      (node (ref "U102") (pin "8") (pinfunction "8_8") (pintype "passive"))
    )
    (net (code "80") (name "unconnected-(U102-VPP-Pad6)") (class "Default")
      (node (ref "U102") (pin "6") (pinfunction "VPP_6") (pintype "passive"))
    )
    (net (code "81") (name "unconnected-(VD101-Pad5)") (class "Default")
      (node (ref "VD101") (pin "5") (pinfunction "5_5") (pintype "passive"))
    )
  )
)
